# silverduino.net
KiCad netlist of a schematic drawn in EAGLE
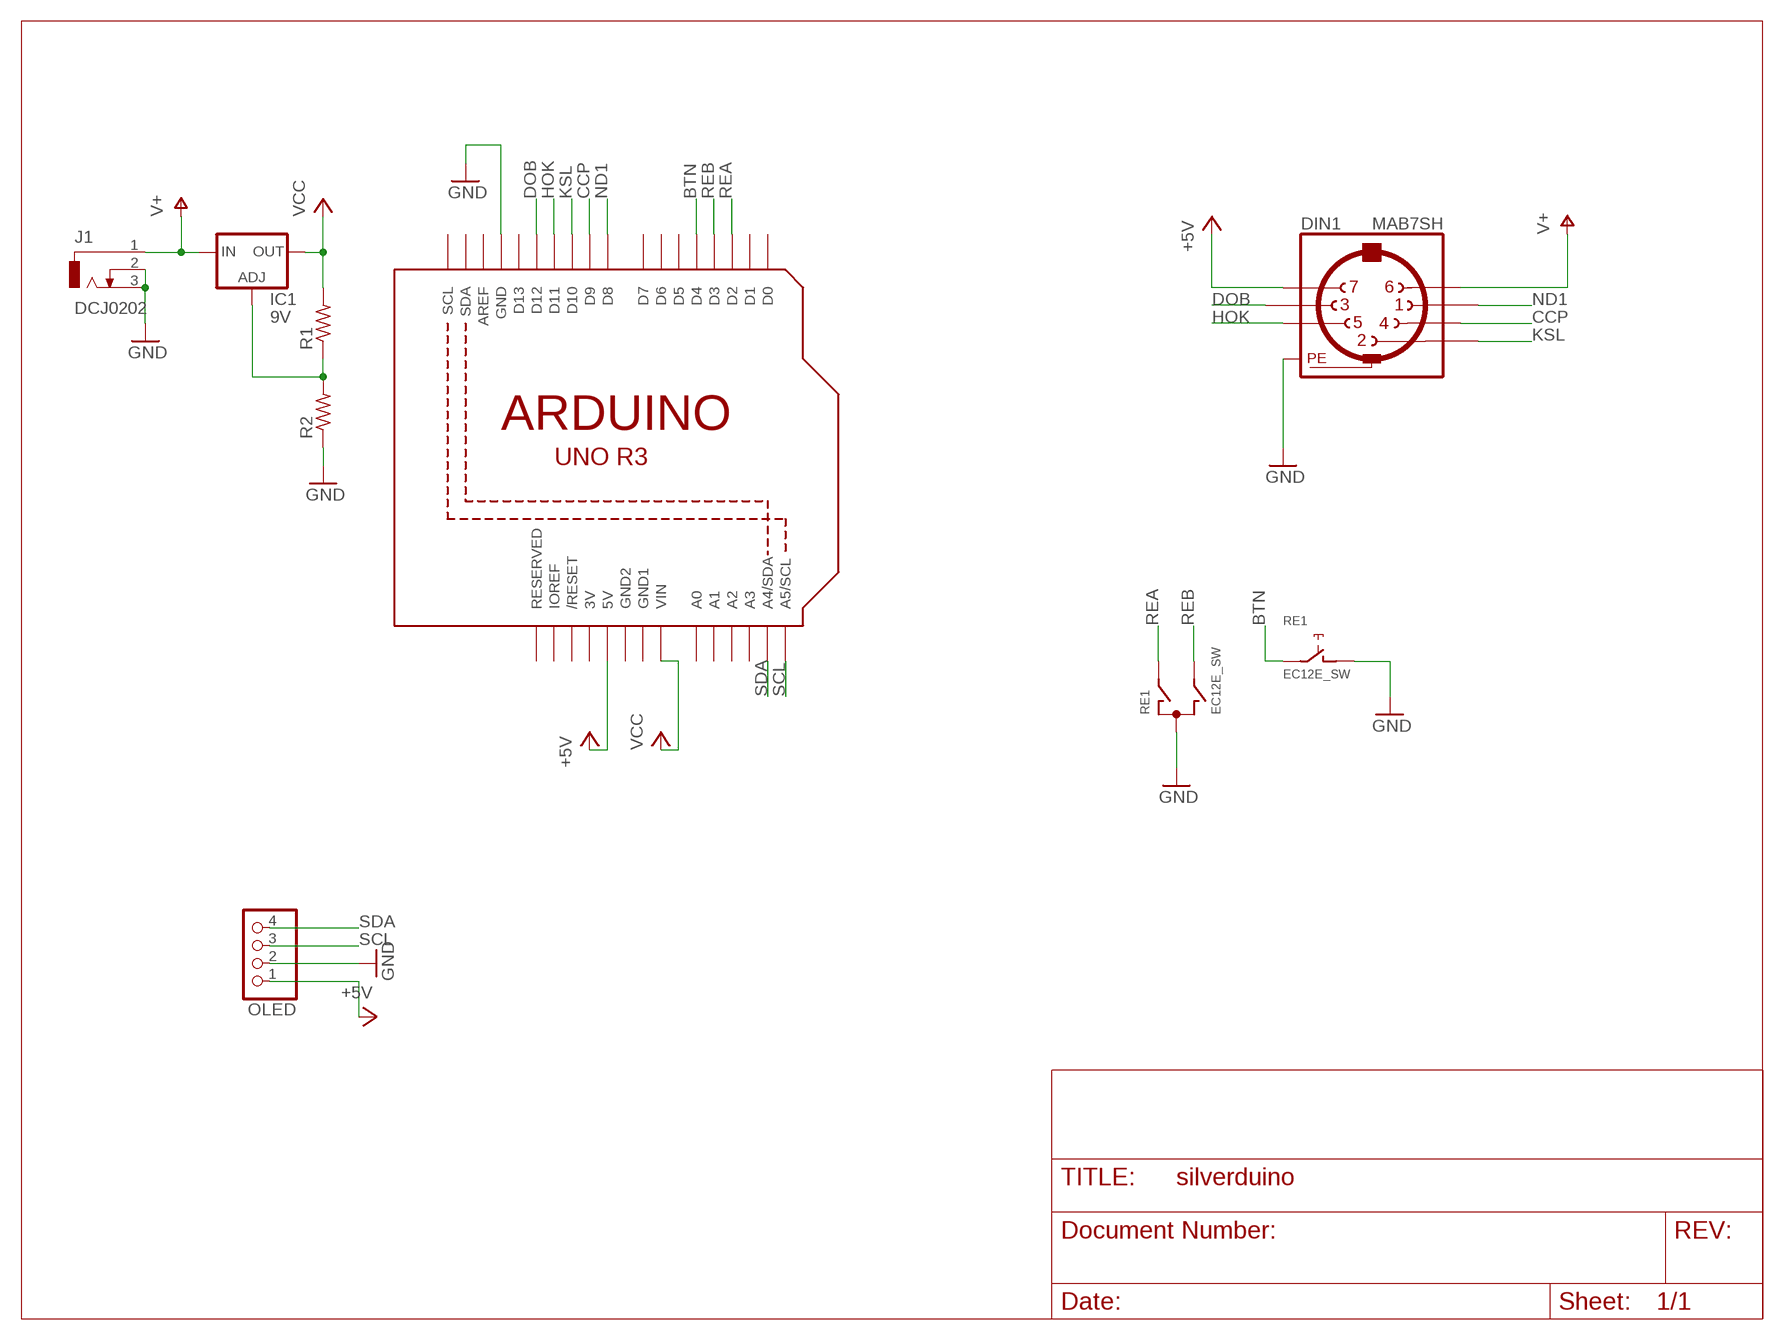
[diagram p0: schematic, sheet 1]

(export (version "E")
  (design (tool "Eeschema 10.0.6"))
  (components
    (comp (ref "DIN1")
      (value "MAB7SH")
      (footprint "eagle-import:MAB7SH")
      (libsource (lib "eagle-import") (part "MAB7SH"))
    )
    (comp (ref "IC1")
      (value "9V")
      (footprint "eagle-import:317TL")
      (libsource (lib "eagle-import") (part "LM317TL"))
    )
    (comp (ref "J1")
      (value "DCJ0202")
      (footprint "eagle-import:DCJ0202")
      (libsource (lib "eagle-import") (part "DCJ0202"))
    )
    (comp (ref "OLED")
      (value "PINHD-1X4")
      (footprint "eagle-import:1X04")
      (libsource (lib "eagle-import") (part "PINHD-1X4"))
    )
    (comp (ref "R1")
      (value "R-US_0207/10")
      (footprint "eagle-import:0207_10")
      (libsource (lib "eagle-import") (part "R-US_0207/10"))
    )
    (comp (ref "R2")
      (value "R-US_0207/10")
      (footprint "eagle-import:0207_10")
      (libsource (lib "eagle-import") (part "R-US_0207/10"))
    )
    (comp (ref "RE1")
      (value "EC12E_SW")
      (footprint "eagle-import:ALPS_EC12E_SW")
      (fields (field (name "MPN") "EC12E2424407"))
      (libsource (lib "eagle-import") (part "EC12E_SW"))
    )
    (comp (ref "U1")
      (value "ARDUINOR3-DIMENSION")
      (footprint "eagle-import:ARDUINOR3")
      (libsource (lib "eagle-import") (part "ARDUINOR3-DIMENSION"))
    )
  )
  (nets
    (net (code "1") (name "+5V") (class "Default")
      (node (ref "DIN1") (pin "7") (pinfunction "7_7") (pintype "passive"))
      (node (ref "OLED") (pin "1") (pinfunction "1_1") (pintype "passive"))
      (node (ref "U1") (pin "5V") (pinfunction "5V_5V") (pintype "power_in"))
    )
    (net (code "2") (name "/3V") (class "Default")
      (node (ref "U1") (pin "3V") (pinfunction "3V_3V") (pintype "power_in"))
    )
    (net (code "3") (name "/BTN") (class "Default")
      (node (ref "RE1") (pin "E") (pinfunction "2_E") (pintype "passive"))
      (node (ref "U1") (pin "D4") (pinfunction "D4_D4") (pintype "bidirectional"))
    )
    (net (code "4") (name "/CCP") (class "Default")
      (node (ref "DIN1") (pin "4") (pinfunction "4_4") (pintype "passive"))
      (node (ref "U1") (pin "D9") (pinfunction "D9_D9") (pintype "bidirectional"))
    )
    (net (code "5") (name "/DOB") (class "Default")
      (node (ref "DIN1") (pin "3") (pinfunction "3_3") (pintype "passive"))
      (node (ref "U1") (pin "D12") (pinfunction "D12_D12") (pintype "bidirectional"))
    )
    (net (code "6") (name "/GND1") (class "Default")
      (node (ref "U1") (pin "GND1") (pinfunction "GND1_GND1") (pintype "power_in"))
    )
    (net (code "7") (name "/GND2") (class "Default")
      (node (ref "U1") (pin "GND2") (pinfunction "GND2_GND2") (pintype "power_in"))
    )
    (net (code "8") (name "/HOK") (class "Default")
      (node (ref "DIN1") (pin "5") (pinfunction "5_5") (pintype "passive"))
      (node (ref "U1") (pin "D11") (pinfunction "D11_D11") (pintype "bidirectional"))
    )
    (net (code "9") (name "/KSL") (class "Default")
      (node (ref "DIN1") (pin "2") (pinfunction "2_2") (pintype "passive"))
      (node (ref "U1") (pin "D10") (pinfunction "D10_D10") (pintype "bidirectional"))
    )
    (net (code "10") (name "/ND1") (class "Default")
      (node (ref "DIN1") (pin "1") (pinfunction "1_1") (pintype "passive"))
      (node (ref "U1") (pin "D8") (pinfunction "D8_D8") (pintype "bidirectional"))
    )
    (net (code "11") (name "/REA") (class "Default")
      (node (ref "RE1") (pin "A") (pinfunction "A_A") (pintype "passive"))
      (node (ref "U1") (pin "D2") (pinfunction "D2_D2") (pintype "bidirectional"))
    )
    (net (code "12") (name "/REB") (class "Default")
      (node (ref "RE1") (pin "B") (pinfunction "B_B") (pintype "passive"))
      (node (ref "U1") (pin "D3") (pinfunction "D3_D3") (pintype "bidirectional"))
    )
    (net (code "13") (name "/SCL") (class "Default")
      (node (ref "OLED") (pin "3") (pinfunction "3_3") (pintype "passive"))
      (node (ref "U1") (pin "A5") (pinfunction "A5/SCL_A5") (pintype "bidirectional"))
    )
    (net (code "14") (name "/SDA") (class "Default")
      (node (ref "OLED") (pin "4") (pinfunction "4_4") (pintype "passive"))
      (node (ref "U1") (pin "A4") (pinfunction "A4/SDA_A4") (pintype "bidirectional"))
    )
    (net (code "15") (name "GND") (class "Default")
      (node (ref "DIN1") (pin "PE") (pinfunction "PE_PE") (pintype "power_in"))
      (node (ref "DIN1") (pin "PE@") (pinfunction "PE_PE@") (pintype "power_in"))
      (node (ref "J1") (pin "2") (pinfunction "2_2") (pintype "passive"))
      (node (ref "J1") (pin "3") (pinfunction "3_3") (pintype "passive"))
      (node (ref "OLED") (pin "2") (pinfunction "2_2") (pintype "passive"))
      (node (ref "R2") (pin "1") (pinfunction "1_1") (pintype "passive"))
      (node (ref "RE1") (pin "C") (pinfunction "C_C") (pintype "passive"))
      (node (ref "RE1") (pin "D") (pinfunction "1_D") (pintype "passive"))
      (node (ref "U1") (pin "GND") (pinfunction "GND_GND") (pintype "power_in"))
    )
    (net (code "16") (name "Net-(IC1-ADJ)") (class "Default")
      (node (ref "IC1") (pin "1") (pinfunction "ADJ_1") (pintype "input"))
      (node (ref "R1") (pin "1") (pinfunction "1_1") (pintype "passive"))
      (node (ref "R2") (pin "2") (pinfunction "2_2") (pintype "passive"))
    )
    (net (code "17") (name "V+") (class "Default")
      (node (ref "DIN1") (pin "6") (pinfunction "6_6") (pintype "passive"))
      (node (ref "IC1") (pin "3") (pinfunction "IN_3") (pintype "input"))
      (node (ref "J1") (pin "1") (pinfunction "1_1") (pintype "passive"))
    )
    (net (code "18") (name "VCC") (class "Default")
      (node (ref "IC1") (pin "2") (pinfunction "OUT_2") (pintype "passive"))
      (node (ref "R1") (pin "2") (pinfunction "2_2") (pintype "passive"))
      (node (ref "U1") (pin "VIN") (pinfunction "VIN_VIN") (pintype "power_in"))
    )
    (net (code "19") (name "unconnected-(U1-PadA0)") (class "Default")
      (node (ref "U1") (pin "A0") (pinfunction "A0_A0") (pintype "bidirectional"))
    )
    (net (code "20") (name "unconnected-(U1-PadA1)") (class "Default")
      (node (ref "U1") (pin "A1") (pinfunction "A1_A1") (pintype "bidirectional"))
    )
    (net (code "21") (name "unconnected-(U1-PadA2)") (class "Default")
      (node (ref "U1") (pin "A2") (pinfunction "A2_A2") (pintype "bidirectional"))
    )
    (net (code "22") (name "unconnected-(U1-PadA3)") (class "Default")
      (node (ref "U1") (pin "A3") (pinfunction "A3_A3") (pintype "bidirectional"))
    )
    (net (code "23") (name "unconnected-(U1-PadAREF)") (class "Default")
      (node (ref "U1") (pin "AREF") (pinfunction "AREF_AREF") (pintype "bidirectional"))
    )
    (net (code "24") (name "unconnected-(U1-PadD0)") (class "Default")
      (node (ref "U1") (pin "D0") (pinfunction "D0_D0") (pintype "bidirectional"))
    )
    (net (code "25") (name "unconnected-(U1-PadD1)") (class "Default")
      (node (ref "U1") (pin "D1") (pinfunction "D1_D1") (pintype "bidirectional"))
    )
    (net (code "26") (name "unconnected-(U1-PadD5)") (class "Default")
      (node (ref "U1") (pin "D5") (pinfunction "D5_D5") (pintype "bidirectional"))
    )
    (net (code "27") (name "unconnected-(U1-PadD6)") (class "Default")
      (node (ref "U1") (pin "D6") (pinfunction "D6_D6") (pintype "bidirectional"))
    )
    (net (code "28") (name "unconnected-(U1-PadD7)") (class "Default")
      (node (ref "U1") (pin "D7") (pinfunction "D7_D7") (pintype "bidirectional"))
    )
    (net (code "29") (name "unconnected-(U1-PadD13)") (class "Default")
      (node (ref "U1") (pin "D13") (pinfunction "D13_D13") (pintype "bidirectional"))
    )
    (net (code "30") (name "unconnected-(U1-PadIOREF)") (class "Default")
      (node (ref "U1") (pin "IOREF") (pinfunction "IOREF_IOREF") (pintype "output"))
    )
    (net (code "31") (name "unconnected-(U1-PadRESERVED)") (class "Default")
      (node (ref "U1") (pin "RESERVED") (pinfunction "RESERVED_RESERVED") (pintype "no_connect"))
    )
    (net (code "32") (name "unconnected-(U1-PadSCL)") (class "Default")
      (node (ref "U1") (pin "SCL") (pinfunction "SCL_SCL") (pintype "bidirectional"))
    )
    (net (code "33") (name "unconnected-(U1-PadSDA)") (class "Default")
      (node (ref "U1") (pin "SDA") (pinfunction "SDA_SDA") (pintype "bidirectional"))
    )
    (net (code "34") (name "unconnected-(U1-{slash}RESET-PadRESET)") (class "Default")
      (node (ref "U1") (pin "RESET") (pinfunction "/RESET_RESET") (pintype "bidirectional"))
    )
  )
)
